# Sheet1.net
KiCad netlist of a schematic drawn in Altium Designer
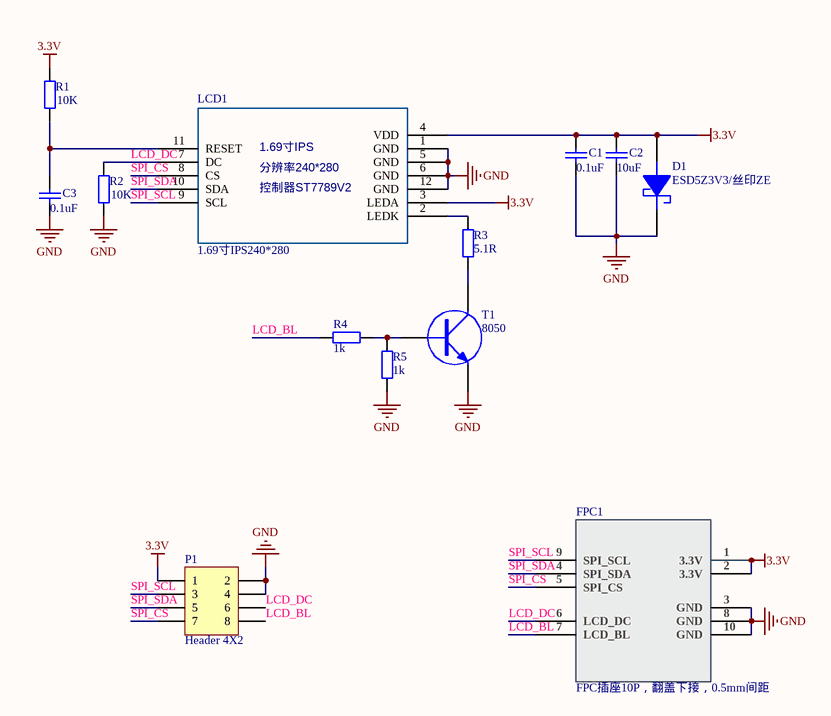
[diagram p0: Sheet1.SchDoc]

(export (version "E")
  (design (tool "Eeschema 10.0.6"))
  (components
    (comp (ref "C1")
      (value "0.1uF")
      (footprint "PCB1:0402-CAP")
      (libsource (lib "1.69_SPI_screen") (part "Cap1"))
    )
    (comp (ref "C2")
      (value "10uF")
      (footprint "PCB1:0402-CAP")
      (libsource (lib "1.69_SPI_screen") (part "Cap1_1"))
    )
    (comp (ref "C3")
      (value "0.1uF")
      (footprint "PCB1:0402-CAP")
      (libsource (lib "1.69_SPI_screen") (part "Cap1"))
    )
    (comp (ref "D1")
      (value "ESD5Z3V3/丝印ZE")
      (footprint "PCB1:SOD523")
      (libsource (lib "1.69_SPI_screen") (part "TVS"))
    )
    (comp (ref "FPC1")
      (value "FPC插座10P，翻盖下接，0.5mm间距")
      (footprint "PCB1:FPC10P-0.5MM")
      (libsource (lib "1.69_SPI_screen") (part "LCD-SPI"))
    )
    (comp (ref "LCD1")
      (value "1.69寸IPS240*280")
      (footprint "PCB1:1.69寸IPS240*280")
      (libsource (lib "1.69_SPI_screen") (part "1.69寸IPS240*280"))
    )
    (comp (ref "P1")
      (value "Header 4X2")
      (footprint "PCB1:HDR2X4")
      (description "Header, 4-Pin, Dual row")
      (libsource (lib "1.69_SPI_screen") (part "Header 4X2"))
    )
    (comp (ref "R1")
      (value "10K")
      (footprint "PCB1:0402-RES")
      (libsource (lib "1.69_SPI_screen") (part "Res"))
    )
    (comp (ref "R2")
      (value "10K")
      (footprint "PCB1:0402-RES")
      (libsource (lib "1.69_SPI_screen") (part "Res"))
    )
    (comp (ref "R3")
      (value "5.1R")
      (footprint "PCB1:0402-res")
      (libsource (lib "1.69_SPI_screen") (part "Res1_1"))
    )
    (comp (ref "R4")
      (value "1k")
      (footprint "PCB1:0402-res")
      (libsource (lib "1.69_SPI_screen") (part "Res1"))
    )
    (comp (ref "R5") (value "1k") (footprint "PCB1:0402-res") (libsource (lib "") (part "Res1_1")))
    (comp (ref "T1")
      (value "8050")
      (footprint "PCB1:SO-G3/C2.25")
      (libsource (lib "1.69_SPI_screen") (part "8050"))
    )
  )
  (nets
    (net (code "1") (name "/LCD_BL") (class "Default")
      (node (ref "FPC1") (pin "7") (pinfunction "LCD_BL_7") (pintype "passive"))
      (node (ref "P1") (pin "8") (pinfunction "8_8") (pintype "passive"))
      (node (ref "R4") (pin "1") (pinfunction "1_1") (pintype "passive"))
    )
    (net (code "2") (name "/LCD_DC") (class "Default")
      (node (ref "FPC1") (pin "6") (pinfunction "LCD_DC_6") (pintype "passive"))
      (node (ref "LCD1") (pin "7") (pinfunction "DC_7") (pintype "passive"))
      (node (ref "P1") (pin "6") (pinfunction "6_6") (pintype "passive"))
      (node (ref "R2") (pin "2") (pinfunction "2_2") (pintype "passive"))
    )
    (net (code "3") (name "/SPI_CS") (class "Default")
      (node (ref "FPC1") (pin "5") (pinfunction "SPI_CS_5") (pintype "passive"))
      (node (ref "LCD1") (pin "8") (pinfunction "CS_8") (pintype "passive"))
      (node (ref "P1") (pin "7") (pinfunction "7_7") (pintype "passive"))
    )
    (net (code "4") (name "/SPI_SCL") (class "Default")
      (node (ref "FPC1") (pin "9") (pinfunction "SPI_SCL_9") (pintype "passive"))
      (node (ref "LCD1") (pin "9") (pinfunction "SCL_9") (pintype "passive"))
      (node (ref "P1") (pin "3") (pinfunction "3_3") (pintype "passive"))
    )
    (net (code "5") (name "/SPI_SDA") (class "Default")
      (node (ref "FPC1") (pin "4") (pinfunction "SPI_SDA_4") (pintype "passive"))
      (node (ref "LCD1") (pin "10") (pinfunction "SDA_10") (pintype "passive"))
      (node (ref "P1") (pin "5") (pinfunction "5_5") (pintype "passive"))
    )
    (net (code "6") (name "3.3V") (class "Default")
      (node (ref "C1") (pin "2") (pinfunction "2_2") (pintype "passive"))
      (node (ref "C2") (pin "2") (pinfunction "2_2") (pintype "passive"))
      (node (ref "D1") (pin "1") (pinfunction "+_1") (pintype "passive"))
      (node (ref "FPC1") (pin "1") (pinfunction "3.3V_1") (pintype "passive"))
      (node (ref "FPC1") (pin "2") (pinfunction "3.3V_2") (pintype "passive"))
      (node (ref "LCD1") (pin "3") (pinfunction "LEDA_3") (pintype "passive"))
      (node (ref "LCD1") (pin "4") (pinfunction "VDD_4") (pintype "passive"))
      (node (ref "P1") (pin "1") (pinfunction "1_1") (pintype "passive"))
      (node (ref "R1") (pin "2") (pinfunction "2_2") (pintype "passive"))
    )
    (net (code "7") (name "GND") (class "Default")
      (node (ref "C1") (pin "1") (pinfunction "1_1") (pintype "passive"))
      (node (ref "C2") (pin "1") (pinfunction "1_1") (pintype "passive"))
      (node (ref "C3") (pin "1") (pinfunction "1_1") (pintype "passive"))
      (node (ref "D1") (pin "2") (pinfunction "-_2") (pintype "passive"))
      (node (ref "FPC1") (pin "10") (pinfunction "GND_10") (pintype "passive"))
      (node (ref "FPC1") (pin "3") (pinfunction "GND_3") (pintype "passive"))
      (node (ref "FPC1") (pin "8") (pinfunction "GND_8") (pintype "passive"))
      (node (ref "LCD1") (pin "1") (pinfunction "GND_1") (pintype "passive"))
      (node (ref "LCD1") (pin "12") (pinfunction "GND_12") (pintype "passive"))
      (node (ref "LCD1") (pin "5") (pinfunction "GND_5") (pintype "passive"))
      (node (ref "LCD1") (pin "6") (pinfunction "GND_6") (pintype "passive"))
      (node (ref "P1") (pin "2") (pinfunction "2_2") (pintype "passive"))
      (node (ref "P1") (pin "4") (pinfunction "4_4") (pintype "passive"))
      (node (ref "R2") (pin "1") (pinfunction "1_1") (pintype "passive"))
      (node (ref "R5") (pin "1") (pinfunction "1_1") (pintype "passive"))
      (node (ref "T1") (pin "1") (pinfunction "E_1") (pintype "passive"))
    )
    (net (code "8") (name "Net-(LCD1-LEDK)") (class "Default")
      (node (ref "LCD1") (pin "2") (pinfunction "LEDK_2") (pintype "passive"))
      (node (ref "R3") (pin "2") (pinfunction "2_2") (pintype "passive"))
    )
    (net (code "9") (name "Net-(LCD1-RESET)") (class "Default")
      (node (ref "C3") (pin "2") (pinfunction "2_2") (pintype "passive"))
      (node (ref "LCD1") (pin "11") (pinfunction "RESET_11") (pintype "passive"))
      (node (ref "R1") (pin "1") (pinfunction "1_1") (pintype "passive"))
    )
    (net (code "10") (name "Net-(T1-B)") (class "Default")
      (node (ref "R4") (pin "2") (pinfunction "2_2") (pintype "passive"))
      (node (ref "R5") (pin "2") (pinfunction "2_2") (pintype "passive"))
      (node (ref "T1") (pin "2") (pinfunction "B_2") (pintype "passive"))
    )
    (net (code "11") (name "Net-(T1-C)") (class "Default")
      (node (ref "R3") (pin "1") (pinfunction "1_1") (pintype "passive"))
      (node (ref "T1") (pin "3") (pinfunction "C_3") (pintype "passive"))
    )
  )
)
